# 2022_V2.net
KiCad netlist of a schematic drawn in Altium Designer
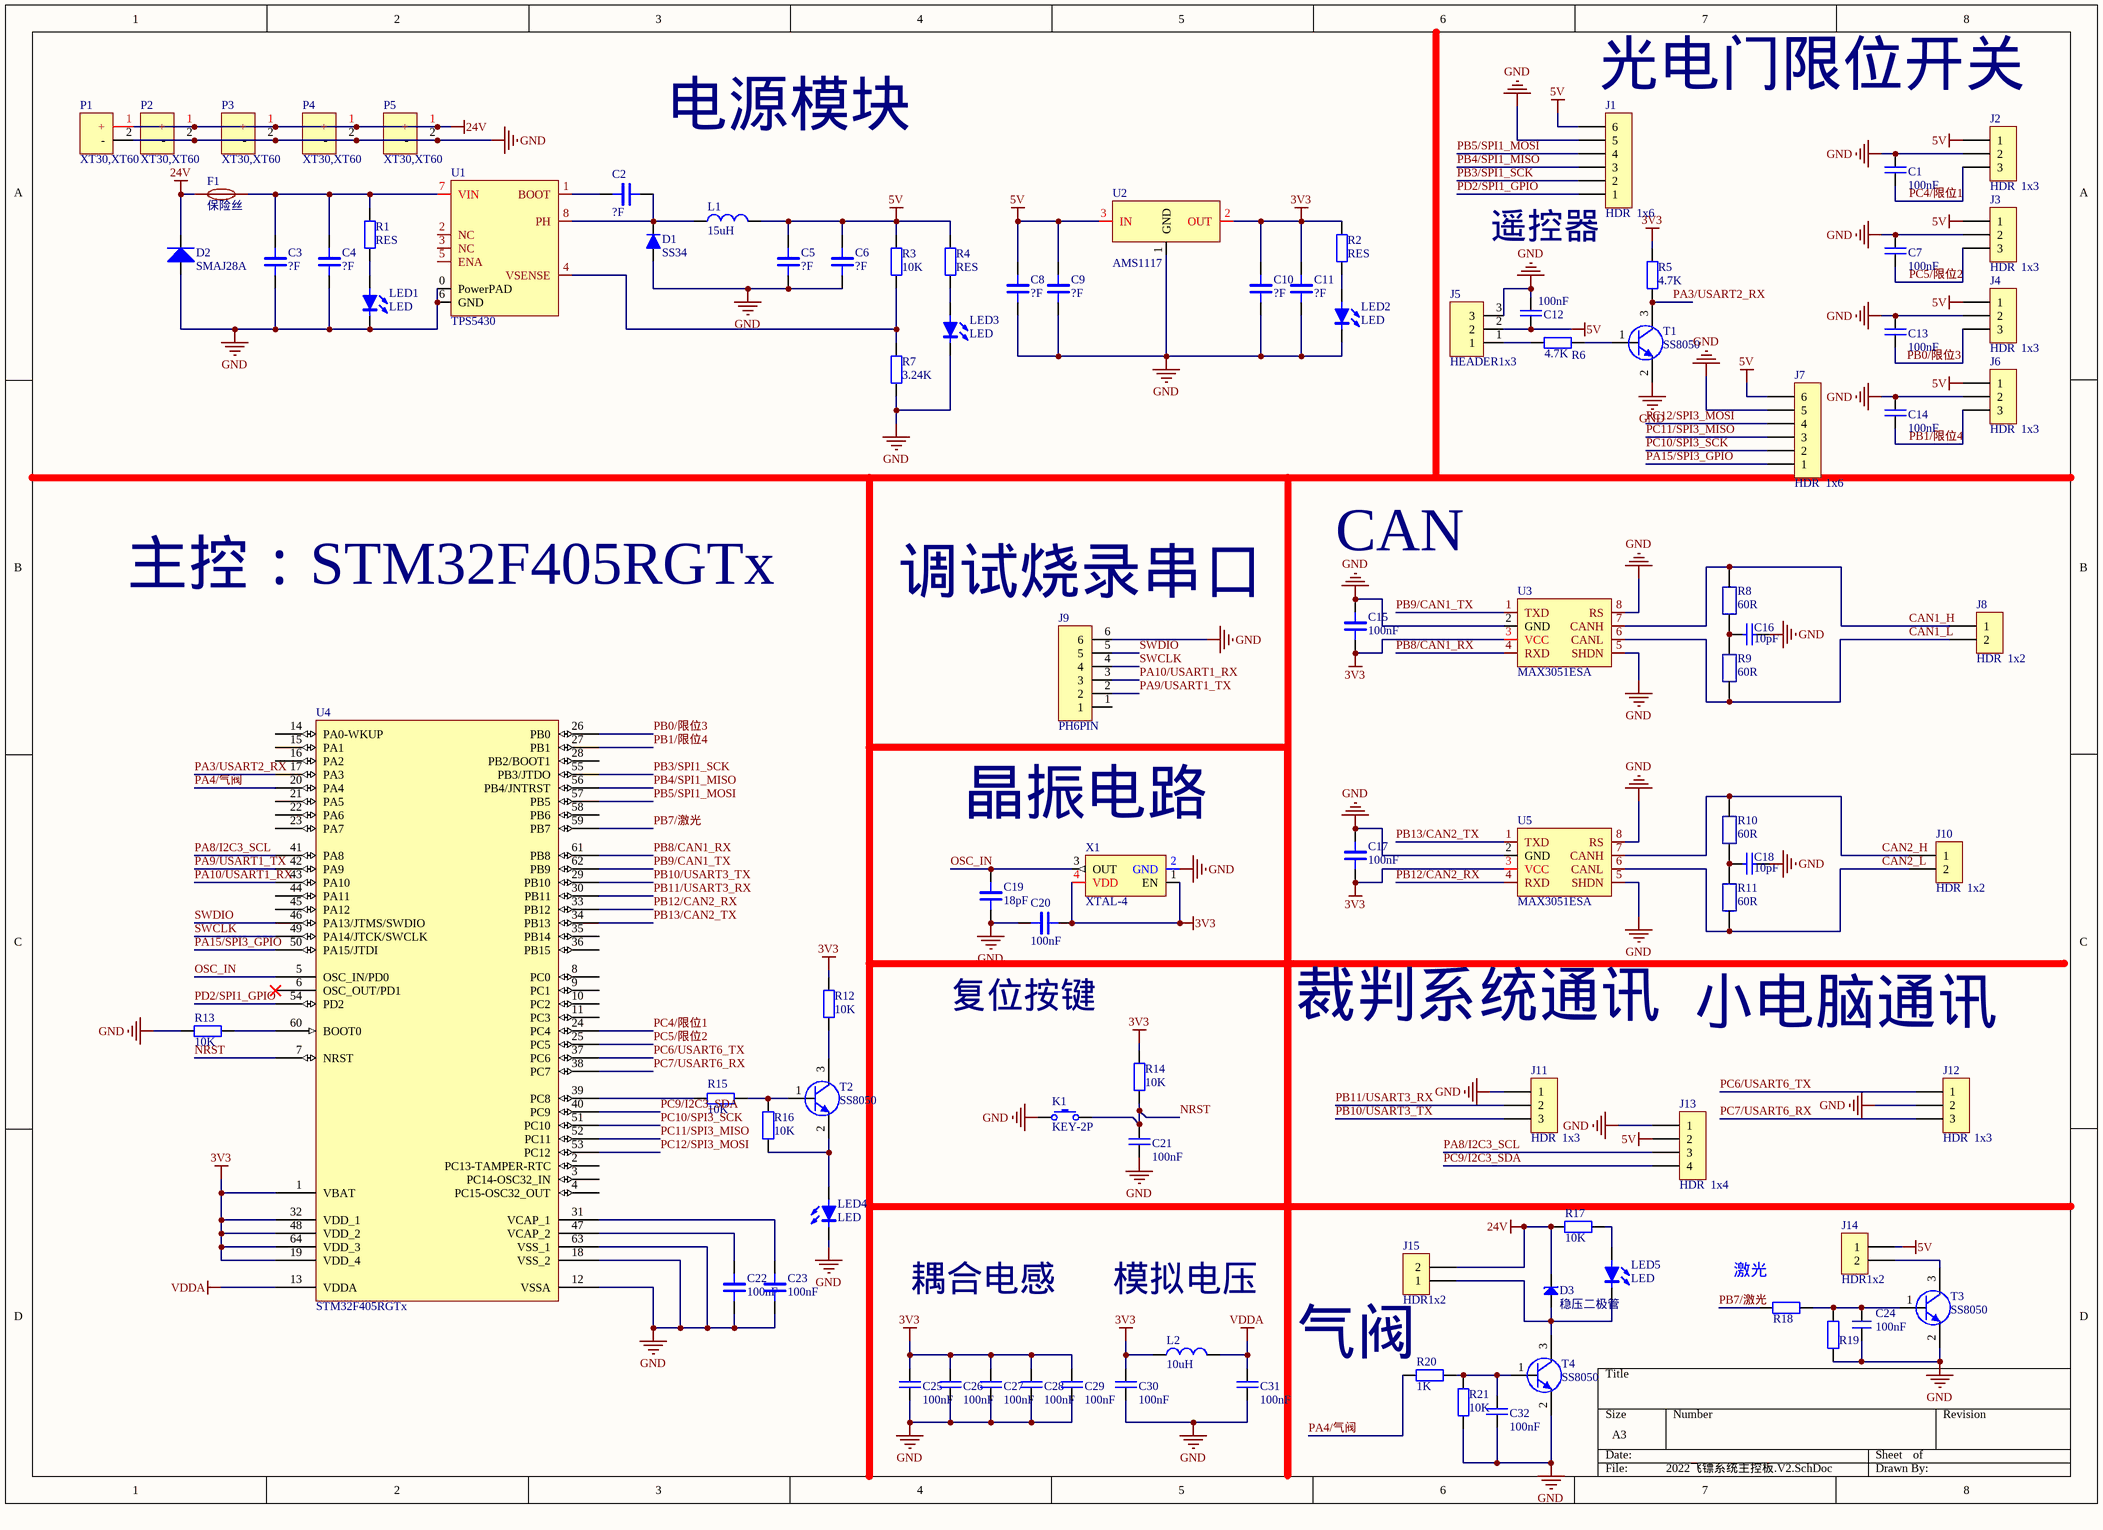
[diagram p0: 2022飞镖系统主控板.V2.SchDoc]

(export (version "E")
  (design (tool "Eeschema 10.0.6"))
  (components
    (comp (ref "C1")
      (value "100nF")
      (footprint "0603_C")
      (fields (field (name "PUBLISHER") "Altium Limited"))
      (libsource (lib "电容-电阻-电感") (part "Cap"))
    )
    (comp (ref "C2")
      (value "?F")
      (footprint "0603_C")
      (description "Capacitor")
      (libsource (lib "General（旧）") (part "CAP"))
    )
    (comp (ref "C3")
      (value "?F")
      (footprint "1206_C")
      (description "Capacitor")
      (libsource (lib "General（旧）") (part "CAP"))
    )
    (comp (ref "C4")
      (value "?F")
      (footprint "1206_C")
      (description "Capacitor")
      (libsource (lib "General（旧）") (part "CAP"))
    )
    (comp (ref "C5")
      (value "?F")
      (footprint "1206_C")
      (description "Capacitor")
      (libsource (lib "General（旧）") (part "CAP"))
    )
    (comp (ref "C6")
      (value "?F")
      (footprint "1206_C")
      (description "Capacitor")
      (libsource (lib "General（旧）") (part "CAP"))
    )
    (comp (ref "C7")
      (value "100nF")
      (footprint "0603_C")
      (fields (field (name "PUBLISHER") "Altium Limited"))
      (libsource (lib "电容-电阻-电感") (part "Cap"))
    )
    (comp (ref "C8")
      (value "?F")
      (footprint "1206_C")
      (description "Capacitor")
      (libsource (lib "General（旧）") (part "CAP"))
    )
    (comp (ref "C9")
      (value "?F")
      (footprint "1206_C")
      (description "Capacitor")
      (libsource (lib "General（旧）") (part "CAP"))
    )
    (comp (ref "C10")
      (value "?F")
      (footprint "1206_C")
      (description "Capacitor")
      (libsource (lib "General（旧）") (part "CAP"))
    )
    (comp (ref "C11")
      (value "?F")
      (footprint "1206_C")
      (description "Capacitor")
      (libsource (lib "General（旧）") (part "CAP"))
    )
    (comp (ref "C12")
      (value "100nF")
      (footprint "0603_C")
      (fields (field (name "PUBLISHER") "Altium Limited"))
      (libsource (lib "电容-电阻-电感") (part "Cap"))
    )
    (comp (ref "C13")
      (value "100nF")
      (footprint "0603_C")
      (fields (field (name "PUBLISHER") "Altium Limited"))
      (libsource (lib "电容-电阻-电感") (part "Cap"))
    )
    (comp (ref "C14")
      (value "100nF")
      (footprint "0603_C")
      (fields (field (name "PUBLISHER") "Altium Limited"))
      (libsource (lib "电容-电阻-电感") (part "Cap"))
    )
    (comp (ref "C15")
      (value "100nF")
      (footprint "0603_C")
      (description "Capacitor")
      (libsource (lib "General（旧）") (part "CAP"))
    )
    (comp (ref "C16") (value "10pF") (footprint "0603_C") (libsource (lib "原理图库") (part "C")))
    (comp (ref "C17")
      (value "100nF")
      (footprint "0603_C")
      (description "Capacitor")
      (libsource (lib "General（旧）") (part "CAP"))
    )
    (comp (ref "C18") (value "10pF") (footprint "0603_C") (libsource (lib "原理图库") (part "C")))
    (comp (ref "C19")
      (value "18pF")
      (footprint "0603_C")
      (description "Capacitor")
      (libsource (lib "General（旧）") (part "CAP"))
    )
    (comp (ref "C20")
      (value "100nF")
      (footprint "0603_C")
      (description "Capacitor")
      (libsource (lib "General（旧）") (part "CAP"))
    )
    (comp (ref "C21")
      (value "100nF")
      (footprint "0603_C")
      (fields (field (name "PUBLISHER") "Altium Limited"))
      (libsource (lib "电容-电阻-电感") (part "Cap"))
    )
    (comp (ref "C22")
      (value "100nF")
      (footprint "0603_C")
      (description "Capacitor")
      (libsource (lib "General（旧）") (part "CAP"))
    )
    (comp (ref "C23")
      (value "100nF")
      (footprint "0603_C")
      (description "Capacitor")
      (libsource (lib "General（旧）") (part "CAP"))
    )
    (comp (ref "C24")
      (value "100nF")
      (footprint "0603_C")
      (fields (field (name "PUBLISHER") "Altium Limited"))
      (libsource (lib "USUAUL") (part "Cap"))
    )
    (comp (ref "C25")
      (value "100nF")
      (footprint "0603_C")
      (fields (field (name "PUBLISHER") "Altium Limited"))
      (libsource (lib "电容-电阻-电感") (part "Cap"))
    )
    (comp (ref "C26")
      (value "100nF")
      (footprint "0603_C")
      (fields (field (name "PUBLISHER") "Altium Limited"))
      (libsource (lib "电容-电阻-电感") (part "Cap"))
    )
    (comp (ref "C27")
      (value "100nF")
      (footprint "0603_C")
      (fields (field (name "PUBLISHER") "Altium Limited"))
      (libsource (lib "电容-电阻-电感") (part "Cap"))
    )
    (comp (ref "C28")
      (value "100nF")
      (footprint "0603_C")
      (fields (field (name "PUBLISHER") "Altium Limited"))
      (libsource (lib "电容-电阻-电感") (part "Cap"))
    )
    (comp (ref "C29")
      (value "100nF")
      (footprint "0603_C")
      (fields (field (name "PUBLISHER") "Altium Limited"))
      (libsource (lib "电容-电阻-电感") (part "Cap"))
    )
    (comp (ref "C30")
      (value "100nF")
      (footprint "0603_C")
      (fields (field (name "PUBLISHER") "Altium Limited"))
      (libsource (lib "电容-电阻-电感") (part "Cap"))
    )
    (comp (ref "C31")
      (value "100nF")
      (footprint "0603_C")
      (fields (field (name "PUBLISHER") "Altium Limited"))
      (libsource (lib "电容-电阻-电感") (part "Cap"))
    )
    (comp (ref "C32")
      (value "100nF")
      (footprint "0603_C")
      (fields (field (name "PUBLISHER") "Altium Limited"))
      (libsource (lib "电容-电阻-电感") (part "Cap"))
    )
    (comp (ref "D1")
      (value "SS34")
      (footprint "SMA(DO-214AC)")
      (description "肖特基二极管")
      (fields
        (field (name "BOM_SUPPLIER PART") "C431540")
        (field (name "BOM_MANUFACTURER PART") "MSK12C02")
        (field (name "CONTRIBUTOR") "LCSC")
      )
      (libsource (lib "General（旧）") (part "SS34"))
    )
    (comp (ref "D2")
      (value "SMAJ28A")
      (footprint "SMA(DO-214AC)")
      (description "TVS")
      (libsource (lib "General（旧）") (part "SMAJ28A"))
    )
    (comp (ref "D3") (value "稳压二极管") (footprint "SOD-323") (libsource (lib "General（旧）") (part "稳压二极管")))
    (comp (ref "F1") (value "保险丝") (footprint "1812_F") (libsource (lib "General（旧）") (part "保险丝")))
    (comp (ref "J1")
      (value "HDR  1x6")
      (footprint "GH 6P 1.25mm 卧 贴")
      (description "Connector")
      (libsource (lib "General（旧）") (part "HDR  1x6"))
    )
    (comp (ref "J2")
      (value "HDR  1x3")
      (footprint "PH 3P 2mm 立 插")
      (description "Connector")
      (libsource (lib "General（旧）") (part "HDR  1x3"))
    )
    (comp (ref "J3")
      (value "HDR  1x3")
      (footprint "PH 3P 2mm 立 插")
      (description "Connector")
      (libsource (lib "General（旧）") (part "HDR  1x3"))
    )
    (comp (ref "J4")
      (value "HDR  1x3")
      (footprint "PH 3P 2mm 立 插")
      (description "Connector")
      (libsource (lib "General（旧）") (part "HDR  1x3"))
    )
    (comp (ref "J5")
      (value "HEADER1x3")
      (footprint "GH 3P 1.25mm 卧 贴")
      (libsource (lib "连接器") (part "HEADER1x3"))
    )
    (comp (ref "J6")
      (value "HDR  1x3")
      (footprint "PH 3P 2mm 立 插")
      (description "Connector")
      (libsource (lib "General（旧）") (part "HDR  1x3"))
    )
    (comp (ref "J7")
      (value "HDR  1x6")
      (footprint "GH 6P 1.25mm 卧 贴")
      (description "Connector")
      (libsource (lib "General（旧）") (part "HDR  1x6"))
    )
    (comp (ref "J8")
      (value "HDR  1x2")
      (footprint "GH 2P 1.25mm 卧 贴")
      (description "Connector")
      (libsource (lib "General（旧）") (part "HDR  1x2"))
    )
    (comp (ref "J9") (value "PH6PIN") (footprint "PH 6P 2mm 立 插") (libsource (lib "连接器") (part "PH 6P")))
    (comp (ref "J10")
      (value "HDR  1x2")
      (footprint "GH 2P 1.25mm 卧 贴")
      (description "Connector")
      (libsource (lib "General（旧）") (part "HDR  1x2"))
    )
    (comp (ref "J11")
      (value "HDR  1x3")
      (footprint "GH 3P 1.25mm 卧 贴")
      (description "Connector")
      (libsource (lib "General（旧）") (part "HDR  1x3"))
    )
    (comp (ref "J12")
      (value "HDR  1x3")
      (footprint "GH 3P 1.25mm 卧 贴")
      (description "Connector")
      (libsource (lib "General（旧）") (part "HDR  1x3"))
    )
    (comp (ref "J13")
      (value "HDR  1x4")
      (footprint "排针排母 4P 2.54mm")
      (description "Connector")
      (libsource (lib "General（旧）") (part "HDR  1x4"))
    )
    (comp (ref "J14")
      (value "HDR1x2")
      (footprint "FPC-SMD_2P-P2.00_DEALON_PH-2PWB")
      (description "Connector")
      (libsource (lib "General") (part "HDR1x2"))
    )
    (comp (ref "J15")
      (value "HDR1x2")
      (footprint "FPC-SMD_2P-P2.00_DEALON_PH-2PWB")
      (description "Connector")
      (libsource (lib "") (part "HDR1x2_1"))
    )
    (comp (ref "K1")
      (value "KEY-2P")
      (footprint "SW-按键")
      (description "Key")
      (libsource (lib "General") (part "KEY-2P"))
    )
    (comp (ref "L1")
      (value "15uH")
      (footprint "SMD_7.3*6.6*3MM_0630")
      (description "Inductor")
      (fields (field (name "PUBLISHER") "Altium Limited"))
      (libsource (lib "General（旧）") (part "Inductor"))
    )
    (comp (ref "L2")
      (value "10uH")
      (footprint "0603_L")
      (description "Inductor")
      (fields (field (name "PUBLISHER") "Altium Limited"))
      (libsource (lib "General（旧）") (part "Inductor"))
    )
    (comp (ref "LED1") (value "LED") (footprint "LED_0603") (libsource (lib "General（旧）") (part "LED")))
    (comp (ref "LED2") (value "LED") (footprint "LED_0603") (libsource (lib "General（旧）") (part "LED")))
    (comp (ref "LED3") (value "LED") (footprint "LED_0603") (libsource (lib "General（旧）") (part "LED")))
    (comp (ref "LED4") (value "LED") (footprint "LED_0603") (libsource (lib "General（旧）") (part "LED")))
    (comp (ref "LED5") (value "LED") (footprint "LED_0603") (libsource (lib "General（旧）") (part "LED")))
    (comp (ref "P1")
      (value "XT30,XT60")
      (footprint "XT30PW-F")
      (description "电源接口")
      (libsource (lib "General（旧）") (part "XT"))
    )
    (comp (ref "P2")
      (value "XT30,XT60")
      (footprint "XT30PW-F")
      (description "电源接口")
      (libsource (lib "General（旧）") (part "XT"))
    )
    (comp (ref "P3")
      (value "XT30,XT60")
      (footprint "XT30PW-F")
      (description "电源接口")
      (libsource (lib "General（旧）") (part "XT"))
    )
    (comp (ref "P4")
      (value "XT30,XT60")
      (footprint "XT30PW-F")
      (description "电源接口")
      (libsource (lib "General（旧）") (part "XT"))
    )
    (comp (ref "P5")
      (value "XT30,XT60")
      (footprint "XT30PW-F")
      (description "电源接口")
      (libsource (lib "General（旧）") (part "XT"))
    )
    (comp (ref "R1")
      (value "RES")
      (footprint "0603_R")
      (description "Resistor")
      (libsource (lib "") (part "RES_1"))
    )
    (comp (ref "R2")
      (value "RES")
      (footprint "0603_R")
      (description "Resistor")
      (libsource (lib "") (part "RES_1"))
    )
    (comp (ref "R3")
      (value "10K")
      (footprint "0603_R")
      (description "Resistor")
      (libsource (lib "") (part "RES_1"))
    )
    (comp (ref "R4")
      (value "RES")
      (footprint "0603_R")
      (description "Resistor")
      (libsource (lib "") (part "RES_1"))
    )
    (comp (ref "R5")
      (value "4.7K")
      (footprint "0603_R")
      (fields (field (name "PUBLISHER") "Altium Limited"))
      (libsource (lib "") (part "Res_1"))
    )
    (comp (ref "R6")
      (value "4.7K")
      (footprint "0603_R")
      (fields (field (name "PUBLISHER") "Altium Limited"))
      (libsource (lib "") (part "Res_2"))
    )
    (comp (ref "R7")
      (value "3.24K")
      (footprint "0603_R")
      (description "Resistor")
      (libsource (lib "") (part "RES_1"))
    )
    (comp (ref "R8") (value "60R") (footprint "0603_R") (libsource (lib "原理图库") (part "R")))
    (comp (ref "R9") (value "60R") (footprint "0603_R") (libsource (lib "原理图库") (part "R")))
    (comp (ref "R10") (value "60R") (footprint "0603_R") (libsource (lib "原理图库") (part "R")))
    (comp (ref "R11") (value "60R") (footprint "0603_R") (libsource (lib "原理图库") (part "R")))
    (comp (ref "R12")
      (value "10K")
      (footprint "0603_R")
      (description "Resistor")
      (libsource (lib "") (part "RES_3"))
    )
    (comp (ref "R13")
      (value "10K")
      (footprint "0603_R")
      (description "Resistor")
      (libsource (lib "General（旧）") (part "RES"))
    )
    (comp (ref "R14")
      (value "10K")
      (footprint "0603_R")
      (fields (field (name "PUBLISHER") "Altium Limited"))
      (libsource (lib "") (part "Res_1"))
    )
    (comp (ref "R15")
      (value "10K")
      (footprint "0603_R")
      (description "Resistor")
      (libsource (lib "") (part "RES_2"))
    )
    (comp (ref "R16")
      (value "10K")
      (footprint "0603_R")
      (description "Resistor")
      (libsource (lib "General（旧）") (part "RES"))
    )
    (comp (ref "R17")
      (value "10K")
      (footprint "0603_R")
      (fields (field (name "PUBLISHER") "Altium Limited"))
      (libsource (lib "电容-电阻-电感") (part "Res"))
    )
    (comp (ref "R18")
      (value "Res")
      (footprint "0603_R")
      (fields (field (name "PUBLISHER") "Altium Limited"))
      (libsource (lib "电容-电阻-电感") (part "Res"))
    )
    (comp (ref "R19")
      (value "Res")
      (footprint "0603_R")
      (fields (field (name "PUBLISHER") "Altium Limited"))
      (libsource (lib "") (part "Res_1"))
    )
    (comp (ref "R20")
      (value "1K")
      (footprint "0603_R")
      (fields (field (name "PUBLISHER") "Altium Limited"))
      (libsource (lib "电容-电阻-电感") (part "Res"))
    )
    (comp (ref "R21")
      (value "10K")
      (footprint "0603_R")
      (fields (field (name "PUBLISHER") "Altium Limited"))
      (libsource (lib "") (part "Res_1"))
    )
    (comp (ref "T1")
      (value "SS8050")
      (footprint "SOT-23")
      (description "NPN")
      (fields (field (name "PUBLISHER") "Altium Limited"))
      (libsource (lib "二极管-晶体管") (part "SS8050"))
    )
    (comp (ref "T2")
      (value "SS8050")
      (footprint "SOT-23")
      (description "NPN")
      (fields (field (name "PUBLISHER") "Altium Limited"))
      (libsource (lib "二极管-晶体管") (part "SS8050"))
    )
    (comp (ref "T3")
      (value "SS8050")
      (footprint "SOT-23")
      (description "NPN")
      (fields (field (name "PUBLISHER") "Altium Limited"))
      (libsource (lib "二极管-晶体管") (part "SS8050"))
    )
    (comp (ref "T4")
      (value "SS8050")
      (footprint "SOT-23")
      (description "NPN")
      (fields (field (name "PUBLISHER") "Altium Limited"))
      (libsource (lib "二极管-晶体管") (part "SS8050"))
    )
    (comp (ref "U1")
      (value "TPS5430")
      (footprint "SOP8-EP")
      (description "DC-DC 降压芯片")
      (libsource (lib "General（旧）") (part "TPS5430"))
    )
    (comp (ref "U2")
      (value "AMS1117")
      (footprint "SOT-223")
      (description "LDO")
      (libsource (lib "General（旧）") (part "AMS1117"))
    )
    (comp (ref "U3")
      (value "MAX3051ESA")
      (footprint "SOP8")
      (description "CAN芯片")
      (libsource (lib "General（旧）") (part "MAX3051ESA"))
    )
    (comp (ref "U4")
      (value "STM32F405RGTx")
      (footprint "LQFP-64_10x10x05P")
      (description "STM32单片机")
      (libsource (lib "General（旧）") (part "STM32F405RGTx"))
    )
    (comp (ref "U5")
      (value "MAX3051ESA")
      (footprint "SOP8")
      (description "CAN芯片")
      (libsource (lib "General（旧）") (part "MAX3051ESA"))
    )
    (comp (ref "X1")
      (value "XTAL-4")
      (footprint "OSC-SMD_4P")
      (description "Oscillator")
      (libsource (lib "General（旧）") (part "XTAL-4"))
    )
  )
  (nets
    (net (code "1") (name "/CAN1_H") (class "Default")
      (node (ref "J8") (pin "1") (pinfunction "1_1") (pintype "passive"))
      (node (ref "R8") (pin "2") (pinfunction "2_2") (pintype "passive"))
      (node (ref "U3") (pin "7") (pinfunction "CANH_7") (pintype "passive"))
    )
    (net (code "2") (name "/CAN1_L") (class "Default")
      (node (ref "J8") (pin "2") (pinfunction "2_2") (pintype "passive"))
      (node (ref "R9") (pin "2") (pinfunction "2_2") (pintype "passive"))
      (node (ref "U3") (pin "6") (pinfunction "CANL_6") (pintype "passive"))
    )
    (net (code "3") (name "/CAN2_H") (class "Default")
      (node (ref "J10") (pin "1") (pinfunction "1_1") (pintype "passive"))
      (node (ref "R10") (pin "2") (pinfunction "2_2") (pintype "passive"))
      (node (ref "U5") (pin "7") (pinfunction "CANH_7") (pintype "passive"))
    )
    (net (code "4") (name "/CAN2_L") (class "Default")
      (node (ref "J10") (pin "2") (pinfunction "2_2") (pintype "passive"))
      (node (ref "R11") (pin "2") (pinfunction "2_2") (pintype "passive"))
      (node (ref "U5") (pin "6") (pinfunction "CANL_6") (pintype "passive"))
    )
    (net (code "5") (name "/NRST") (class "Default")
      (node (ref "C21") (pin "1") (pinfunction "1_1") (pintype "passive"))
      (node (ref "K1") (pin "2") (pinfunction "2_2") (pintype "passive"))
      (node (ref "R14") (pin "1") (pinfunction "1_1") (pintype "passive"))
      (node (ref "U4") (pin "7") (pinfunction "NRST_7") (pintype "bidirectional"))
    )
    (net (code "6") (name "/OSC_IN") (class "Default")
      (node (ref "C19") (pin "2") (pinfunction "2_2") (pintype "passive"))
      (node (ref "U4") (pin "5") (pinfunction "OSC_IN/PD0_5") (pintype "passive"))
      (node (ref "X1") (pin "3") (pinfunction "OUT_3") (pintype "output"))
    )
    (net (code "7") (name "/PA3{slash}USART2_RX") (class "Default")
      (node (ref "R5") (pin "1") (pinfunction "1_1") (pintype "passive"))
      (node (ref "T1") (pin "3") (pinfunction "C_3") (pintype "passive"))
      (node (ref "U4") (pin "17") (pinfunction "PA3_17") (pintype "bidirectional"))
    )
    (net (code "8") (name "/PA4{slash}气阀") (class "Default")
      (node (ref "R20") (pin "1") (pinfunction "1_1") (pintype "passive"))
      (node (ref "U4") (pin "20") (pinfunction "PA4_20") (pintype "bidirectional"))
    )
    (net (code "9") (name "/PA8{slash}I2C3_SCL") (class "Default")
      (node (ref "J13") (pin "3") (pinfunction "3_3") (pintype "passive"))
      (node (ref "U4") (pin "41") (pinfunction "PA8_41") (pintype "bidirectional"))
    )
    (net (code "10") (name "/PA9{slash}USART1_TX") (class "Default")
      (node (ref "J9") (pin "2") (pinfunction "2_2") (pintype "passive"))
      (node (ref "U4") (pin "42") (pinfunction "PA9_42") (pintype "bidirectional"))
    )
    (net (code "11") (name "/PA10{slash}USART1_RX") (class "Default")
      (node (ref "J9") (pin "3") (pinfunction "3_3") (pintype "passive"))
      (node (ref "U4") (pin "43") (pinfunction "PA10_43") (pintype "bidirectional"))
    )
    (net (code "12") (name "/PA15{slash}SPI3_GPIO") (class "Default")
      (node (ref "J7") (pin "1") (pinfunction "1_1") (pintype "passive"))
      (node (ref "U4") (pin "50") (pinfunction "PA15/JTDI_50") (pintype "bidirectional"))
    )
    (net (code "13") (name "/PB0{slash}限位3") (class "Default")
      (node (ref "C13") (pin "2") (pinfunction "2_2") (pintype "passive"))
      (node (ref "J4") (pin "3") (pinfunction "3_3") (pintype "passive"))
      (node (ref "U4") (pin "26") (pinfunction "PB0_26") (pintype "bidirectional"))
    )
    (net (code "14") (name "/PB1{slash}限位4") (class "Default")
      (node (ref "C14") (pin "2") (pinfunction "2_2") (pintype "passive"))
      (node (ref "J6") (pin "3") (pinfunction "3_3") (pintype "passive"))
      (node (ref "U4") (pin "27") (pinfunction "PB1_27") (pintype "bidirectional"))
    )
    (net (code "15") (name "/PB3{slash}SPI1_SCK") (class "Default")
      (node (ref "J1") (pin "2") (pinfunction "2_2") (pintype "passive"))
      (node (ref "U4") (pin "55") (pinfunction "PB3/JTDO_55") (pintype "bidirectional"))
    )
    (net (code "16") (name "/PB4{slash}SPI1_MISO") (class "Default")
      (node (ref "J1") (pin "3") (pinfunction "3_3") (pintype "passive"))
      (node (ref "U4") (pin "56") (pinfunction "PB4/JNTRST_56") (pintype "bidirectional"))
    )
    (net (code "17") (name "/PB5{slash}SPI1_MOSI") (class "Default")
      (node (ref "J1") (pin "4") (pinfunction "4_4") (pintype "passive"))
      (node (ref "U4") (pin "57") (pinfunction "PB5_57") (pintype "bidirectional"))
    )
    (net (code "18") (name "/PB7{slash}激光") (class "Default")
      (node (ref "R18") (pin "1") (pinfunction "1_1") (pintype "passive"))
      (node (ref "U4") (pin "59") (pinfunction "PB7_59") (pintype "bidirectional"))
    )
    (net (code "19") (name "/PB8{slash}CAN1_RX") (class "Default")
      (node (ref "U3") (pin "4") (pinfunction "RXD_4") (pintype "passive"))
      (node (ref "U4") (pin "61") (pinfunction "PB8_61") (pintype "bidirectional"))
    )
    (net (code "20") (name "/PB9{slash}CAN1_TX") (class "Default")
      (node (ref "U3") (pin "1") (pinfunction "TXD_1") (pintype "passive"))
      (node (ref "U4") (pin "62") (pinfunction "PB9_62") (pintype "bidirectional"))
    )
    (net (code "21") (name "/PB10{slash}USART3_TX") (class "Default")
      (node (ref "J11") (pin "3") (pinfunction "3_3") (pintype "passive"))
      (node (ref "U4") (pin "29") (pinfunction "PB10_29") (pintype "bidirectional"))
    )
    (net (code "22") (name "/PB11{slash}USART3_RX") (class "Default")
      (node (ref "J11") (pin "2") (pinfunction "2_2") (pintype "passive"))
      (node (ref "U4") (pin "30") (pinfunction "PB11_30") (pintype "bidirectional"))
    )
    (net (code "23") (name "/PB12{slash}CAN2_RX") (class "Default")
      (node (ref "U4") (pin "33") (pinfunction "PB12_33") (pintype "bidirectional"))
      (node (ref "U5") (pin "4") (pinfunction "RXD_4") (pintype "passive"))
    )
    (net (code "24") (name "/PB13{slash}CAN2_TX") (class "Default")
      (node (ref "U4") (pin "34") (pinfunction "PB13_34") (pintype "bidirectional"))
      (node (ref "U5") (pin "1") (pinfunction "TXD_1") (pintype "passive"))
    )
    (net (code "25") (name "/PC4{slash}限位1") (class "Default")
      (node (ref "C1") (pin "2") (pinfunction "2_2") (pintype "passive"))
      (node (ref "J2") (pin "3") (pinfunction "3_3") (pintype "passive"))
      (node (ref "U4") (pin "24") (pinfunction "PC4_24") (pintype "bidirectional"))
    )
    (net (code "26") (name "/PC5{slash}限位2") (class "Default")
      (node (ref "C7") (pin "2") (pinfunction "2_2") (pintype "passive"))
      (node (ref "J3") (pin "3") (pinfunction "3_3") (pintype "passive"))
      (node (ref "U4") (pin "25") (pinfunction "PC5_25") (pintype "bidirectional"))
    )
    (net (code "27") (name "/PC6{slash}USART6_TX") (class "Default")
      (node (ref "J12") (pin "1") (pinfunction "1_1") (pintype "passive"))
      (node (ref "U4") (pin "37") (pinfunction "PC6_37") (pintype "bidirectional"))
    )
    (net (code "28") (name "/PC7{slash}USART6_RX") (class "Default")
      (node (ref "J12") (pin "3") (pinfunction "3_3") (pintype "passive"))
      (node (ref "U4") (pin "38") (pinfunction "PC7_38") (pintype "bidirectional"))
    )
    (net (code "29") (name "/PC9{slash}I2C3_SDA") (class "Default")
      (node (ref "J13") (pin "4") (pinfunction "4_4") (pintype "passive"))
      (node (ref "U4") (pin "40") (pinfunction "PC9_40") (pintype "bidirectional"))
    )
    (net (code "30") (name "/PC10{slash}SPI3_SCK") (class "Default")
      (node (ref "J7") (pin "2") (pinfunction "2_2") (pintype "passive"))
      (node (ref "U4") (pin "51") (pinfunction "PC10_51") (pintype "bidirectional"))
    )
    (net (code "31") (name "/PC11{slash}SPI3_MISO") (class "Default")
      (node (ref "J7") (pin "3") (pinfunction "3_3") (pintype "passive"))
      (node (ref "U4") (pin "52") (pinfunction "PC11_52") (pintype "bidirectional"))
    )
    (net (code "32") (name "/PC12{slash}SPI3_MOSI") (class "Default")
      (node (ref "J7") (pin "4") (pinfunction "4_4") (pintype "passive"))
      (node (ref "U4") (pin "53") (pinfunction "PC12_53") (pintype "bidirectional"))
    )
    (net (code "33") (name "/PD2{slash}SPI1_GPIO") (class "Default")
      (node (ref "J1") (pin "1") (pinfunction "1_1") (pintype "passive"))
      (node (ref "U4") (pin "54") (pinfunction "PD2_54") (pintype "bidirectional"))
    )
    (net (code "34") (name "/SWCLK") (class "Default")
      (node (ref "J9") (pin "4") (pinfunction "4_4") (pintype "passive"))
      (node (ref "U4") (pin "49") (pinfunction "PA14/JTCK/SWCLK_49") (pintype "bidirectional"))
    )
    (net (code "35") (name "/SWDIO") (class "Default")
      (node (ref "J9") (pin "5") (pinfunction "5_5") (pintype "passive"))
      (node (ref "U4") (pin "46") (pinfunction "PA13/JTMS/SWDIO_46") (pintype "bidirectional"))
    )
    (net (code "36") (name "3V3") (class "Default")
      (node (ref "C10") (pin "2") (pinfunction "2_2") (pintype "passive"))
      (node (ref "C11") (pin "2") (pinfunction "2_2") (pintype "passive"))
      (node (ref "C15") (pin "2") (pinfunction "2_2") (pintype "passive"))
      (node (ref "C17") (pin "2") (pinfunction "2_2") (pintype "passive"))
      (node (ref "C20") (pin "2") (pinfunction "2_2") (pintype "passive"))
      (node (ref "C25") (pin "1") (pinfunction "1_1") (pintype "passive"))
      (node (ref "C26") (pin "1") (pinfunction "1_1") (pintype "passive"))
      (node (ref "C27") (pin "1") (pinfunction "1_1") (pintype "passive"))
      (node (ref "C28") (pin "1") (pinfunction "1_1") (pintype "passive"))
      (node (ref "C29") (pin "1") (pinfunction "1_1") (pintype "passive"))
      (node (ref "C30") (pin "1") (pinfunction "1_1") (pintype "passive"))
      (node (ref "L2") (pin "1") (pinfunction "1_1") (pintype "passive"))
      (node (ref "R12") (pin "1") (pinfunction "1_1") (pintype "passive"))
      (node (ref "R14") (pin "2") (pinfunction "2_2") (pintype "passive"))
      (node (ref "R2") (pin "2") (pinfunction "2_2") (pintype "passive"))
      (node (ref "R5") (pin "2") (pinfunction "2_2") (pintype "passive"))
      (node (ref "U2") (pin "2") (pinfunction "OUT_2") (pintype "passive"))
      (node (ref "U3") (pin "3") (pinfunction "VCC_3") (pintype "passive"))
      (node (ref "U4") (pin "1") (pinfunction "VBAT_1") (pintype "power_in"))
      (node (ref "U4") (pin "19") (pinfunction "VDD_4_19") (pintype "power_in"))
      (node (ref "U4") (pin "32") (pinfunction "VDD_1_32") (pintype "power_in"))
      (node (ref "U4") (pin "48") (pinfunction "VDD_2_48") (pintype "power_in"))
      (node (ref "U4") (pin "64") (pinfunction "VDD_3_64") (pintype "power_in"))
      (node (ref "U5") (pin "3") (pinfunction "VCC_3") (pintype "passive"))
      (node (ref "X1") (pin "1") (pinfunction "EN_1") (pintype "passive"))
      (node (ref "X1") (pin "4") (pinfunction "VDD_4") (pintype "power_in"))
    )
    (net (code "37") (name "5V") (class "Default")
      (node (ref "C12") (pin "1") (pinfunction "1_1") (pintype "passive"))
      (node (ref "C5") (pin "2") (pinfunction "2_2") (pintype "passive"))
      (node (ref "C6") (pin "2") (pinfunction "2_2") (pintype "passive"))
      (node (ref "C8") (pin "2") (pinfunction "2_2") (pintype "passive"))
      (node (ref "C9") (pin "2") (pinfunction "2_2") (pintype "passive"))
      (node (ref "J1") (pin "6") (pinfunction "6_6") (pintype "passive"))
      (node (ref "J13") (pin "2") (pinfunction "2_2") (pintype "passive"))
      (node (ref "J14") (pin "1") (pinfunction "1_1") (pintype "passive"))
      (node (ref "J2") (pin "1") (pinfunction "1_1") (pintype "passive"))
      (node (ref "J3") (pin "1") (pinfunction "1_1") (pintype "passive"))
      (node (ref "J4") (pin "1") (pinfunction "1_1") (pintype "passive"))
      (node (ref "J5") (pin "2") (pinfunction "2_2") (pintype "passive"))
      (node (ref "J6") (pin "1") (pinfunction "1_1") (pintype "passive"))
      (node (ref "J7") (pin "6") (pinfunction "6_6") (pintype "passive"))
      (node (ref "L1") (pin "2") (pinfunction "2_2") (pintype "passive"))
      (node (ref "R3") (pin "2") (pinfunction "2_2") (pintype "passive"))
      (node (ref "R4") (pin "2") (pinfunction "2_2") (pintype "passive"))
      (node (ref "U2") (pin "3") (pinfunction "IN_3") (pintype "passive"))
    )
    (net (code "38") (name "24V") (class "Default")
      (node (ref "D2") (pin "2") (pinfunction "K_2") (pintype "passive"))
      (node (ref "D3") (pin "2") (pinfunction "K_2") (pintype "passive"))
      (node (ref "F1") (pin "1") (pinfunction "1_1") (pintype "passive"))
      (node (ref "J15") (pin "2") (pinfunction "2_2") (pintype "passive"))
      (node (ref "P1") (pin "1") (pinfunction "+_1") (pintype "passive"))
      (node (ref "P2") (pin "1") (pinfunction "+_1") (pintype "passive"))
      (node (ref "P3") (pin "1") (pinfunction "+_1") (pintype "passive"))
      (node (ref "P4") (pin "1") (pinfunction "+_1") (pintype "passive"))
      (node (ref "P5") (pin "1") (pinfunction "+_1") (pintype "passive"))
      (node (ref "R17") (pin "1") (pinfunction "1_1") (pintype "passive"))
    )
    (net (code "39") (name "GND") (class "Default")
      (node (ref "C1") (pin "1") (pinfunction "1_1") (pintype "passive"))
      (node (ref "C10") (pin "1") (pinfunction "1_1") (pintype "passive"))
      (node (ref "C11") (pin "1") (pinfunction "1_1") (pintype "passive"))
      (node (ref "C12") (pin "2") (pinfunction "2_2") (pintype "passive"))
      (node (ref "C13") (pin "1") (pinfunction "1_1") (pintype "passive"))
      (node (ref "C14") (pin "1") (pinfunction "1_1") (pintype "passive"))
      (node (ref "C15") (pin "1") (pinfunction "1_1") (pintype "passive"))
      (node (ref "C16") (pin "2") (pinfunction "2_2") (pintype "passive"))
      (node (ref "C17") (pin "1") (pinfunction "1_1") (pintype "passive"))
      (node (ref "C18") (pin "2") (pinfunction "2_2") (pintype "passive"))
      (node (ref "C19") (pin "1") (pinfunction "1_1") (pintype "passive"))
      (node (ref "C20") (pin "1") (pinfunction "1_1") (pintype "passive"))
      (node (ref "C21") (pin "2") (pinfunction "2_2") (pintype "passive"))
      (node (ref "C22") (pin "1") (pinfunction "1_1") (pintype "passive"))
      (node (ref "C23") (pin "1") (pinfunction "1_1") (pintype "passive"))
      (node (ref "C24") (pin "1") (pinfunction "1_1") (pintype "passive"))
      (node (ref "C25") (pin "2") (pinfunction "2_2") (pintype "passive"))
      (node (ref "C26") (pin "2") (pinfunction "2_2") (pintype "passive"))
      (node (ref "C27") (pin "2") (pinfunction "2_2") (pintype "passive"))
      (node (ref "C28") (pin "2") (pinfunction "2_2") (pintype "passive"))
      (node (ref "C29") (pin "2") (pinfunction "2_2") (pintype "passive"))
      (node (ref "C3") (pin "1") (pinfunction "1_1") (pintype "passive"))
      (node (ref "C30") (pin "2") (pinfunction "2_2") (pintype "passive"))
      (node (ref "C31") (pin "2") (pinfunction "2_2") (pintype "passive"))
      (node (ref "C32") (pin "2") (pinfunction "2_2") (pintype "passive"))
      (node (ref "C4") (pin "1") (pinfunction "1_1") (pintype "passive"))
      (node (ref "C5") (pin "1") (pinfunction "1_1") (pintype "passive"))
      (node (ref "C6") (pin "1") (pinfunction "1_1") (pintype "passive"))
      (node (ref "C7") (pin "1") (pinfunction "1_1") (pintype "passive"))
      (node (ref "C8") (pin "1") (pinfunction "1_1") (pintype "passive"))
      (node (ref "C9") (pin "1") (pinfunction "1_1") (pintype "passive"))
      (node (ref "D1") (pin "1") (pinfunction "1_1") (pintype "passive"))
      (node (ref "D2") (pin "1") (pinfunction "A_1") (pintype "passive"))
      (node (ref "J1") (pin "5") (pinfunction "5_5") (pintype "passive"))
      (node (ref "J11") (pin "1") (pinfunction "1_1") (pintype "passive"))
      (node (ref "J12") (pin "2") (pinfunction "2_2") (pintype "passive"))
      (node (ref "J13") (pin "1") (pinfunction "1_1") (pintype "passive"))
      (node (ref "J2") (pin "2") (pinfunction "2_2") (pintype "passive"))
      (node (ref "J3") (pin "2") (pinfunction "2_2") (pintype "passive"))
      (node (ref "J4") (pin "2") (pinfunction "2_2") (pintype "passive"))
      (node (ref "J5") (pin "3") (pinfunction "3_3") (pintype "passive"))
      (node (ref "J6") (pin "2") (pinfunction "2_2") (pintype "passive"))
      (node (ref "J7") (pin "5") (pinfunction "5_5") (pintype "passive"))
      (node (ref "J9") (pin "6") (pinfunction "6_6") (pintype "passive"))
      (node (ref "K1") (pin "1") (pinfunction "1_1") (pintype "passive"))
      (node (ref "LED1") (pin "2") (pinfunction "C_2") (pintype "passive"))
      (node (ref "LED2") (pin "2") (pinfunction "C_2") (pintype "passive"))
      (node (ref "LED3") (pin "2") (pinfunction "C_2") (pintype "passive"))
      (node (ref "LED4") (pin "2") (pinfunction "C_2") (pintype "passive"))
      (node (ref "P1") (pin "2") (pinfunction "-_2") (pintype "passive"))
      (node (ref "P2") (pin "2") (pinfunction "-_2") (pintype "passive"))
      (node (ref "P3") (pin "2") (pinfunction "-_2") (pintype "passive"))
      (node (ref "P4") (pin "2") (pinfunction "-_2") (pintype "passive"))
      (node (ref "P5") (pin "2") (pinfunction "-_2") (pintype "passive"))
      (node (ref "R13") (pin "1") (pinfunction "1_1") (pintype "passive"))
      (node (ref "R19") (pin "1") (pinfunction "1_1") (pintype "passive"))
      (node (ref "R21") (pin "1") (pinfunction "1_1") (pintype "passive"))
      (node (ref "R7") (pin "1") (pinfunction "1_1") (pintype "passive"))
      (node (ref "T1") (pin "2") (pinfunction "E_2") (pintype "passive"))
      (node (ref "T3") (pin "2") (pinfunction "E_2") (pintype "passive"))
      (node (ref "T4") (pin "2") (pinfunction "E_2") (pintype "passive"))
      (node (ref "U1") (pin "0") (pinfunction "PowerPAD_0") (pintype "passive"))
      (node (ref "U1") (pin "6") (pinfunction "GND_6") (pintype "passive"))
      (node (ref "U2") (pin "1") (pinfunction "GND_1") (pintype "passive"))
      (node (ref "U3") (pin "2") (pinfunction "GND_2") (pintype "passive"))
      (node (ref "U3") (pin "5") (pinfunction "SHDN_5") (pintype "passive"))
      (node (ref "U3") (pin "8") (pinfunction "RS_8") (pintype "passive"))
      (node (ref "U4") (pin "12") (pinfunction "VSSA_12") (pintype "passive"))
      (node (ref "U4") (pin "18") (pinfunction "VSS_2_18") (pintype "passive"))
      (node (ref "U4") (pin "63") (pinfunction "VSS_1_63") (pintype "passive"))
      (node (ref "U5") (pin "2") (pinfunction "GND_2") (pintype "passive"))
      (node (ref "U5") (pin "5") (pinfunction "SHDN_5") (pintype "passive"))
      (node (ref "U5") (pin "8") (pinfunction "RS_8") (pintype "passive"))
      (node (ref "X1") (pin "2") (pinfunction "GND_2") (pintype "passive"))
    )
    (net (code "40") (name "Net-(C16-Pad1)") (class "Default")
      (node (ref "C16") (pin "1") (pinfunction "1_1") (pintype "passive"))
      (node (ref "R8") (pin "1") (pinfunction "1_1") (pintype "passive"))
      (node (ref "R9") (pin "1") (pinfunction "1_1") (pintype "passive"))
    )
    (net (code "41") (name "Net-(C18-Pad1)") (class "Default")
      (node (ref "C18") (pin "1") (pinfunction "1_1") (pintype "passive"))
      (node (ref "R10") (pin "1") (pinfunction "1_1") (pintype "passive"))
      (node (ref "R11") (pin "1") (pinfunction "1_1") (pintype "passive"))
    )
    (net (code "42") (name "Net-(D3-A)") (class "Default")
      (node (ref "D3") (pin "1") (pinfunction "A_1") (pintype "passive"))
      (node (ref "J15") (pin "1") (pinfunction "1_1") (pintype "passive"))
      (node (ref "LED5") (pin "2") (pinfunction "C_2") (pintype "passive"))
      (node (ref "T4") (pin "3") (pinfunction "C_3") (pintype "passive"))
    )
    (net (code "43") (name "Net-(J5-Pad1)") (class "Default")
      (node (ref "J5") (pin "1") (pinfunction "1_1") (pintype "power_in"))
      (node (ref "R6") (pin "2") (pinfunction "2_2") (pintype "passive"))
    )
    (net (code "44") (name "Net-(LED1-A)") (class "Default")
      (node (ref "LED1") (pin "1") (pinfunction "A_1") (pintype "passive"))
      (node (ref "R1") (pin "1") (pinfunction "1_1") (pintype "passive"))
    )
    (net (code "45") (name "Net-(LED2-A)") (class "Default")
      (node (ref "LED2") (pin "1") (pinfunction "A_1") (pintype "passive"))
      (node (ref "R2") (pin "1") (pinfunction "1_1") (pintype "passive"))
    )
    (net (code "46") (name "Net-(LED3-A)") (class "Default")
      (node (ref "LED3") (pin "1") (pinfunction "A_1") (pintype "passive"))
      (node (ref "R4") (pin "1") (pinfunction "1_1") (pintype "passive"))
    )
    (net (code "47") (name "Net-(LED4-A)") (class "Default")
      (node (ref "LED4") (pin "1") (pinfunction "A_1") (pintype "passive"))
      (node (ref "R16") (pin "1") (pinfunction "1_1") (pintype "passive"))
      (node (ref "T2") (pin "2") (pinfunction "E_2") (pintype "passive"))
    )
    (net (code "48") (name "Net-(LED5-A)") (class "Default")
      (node (ref "LED5") (pin "1") (pinfunction "A_1") (pintype "passive"))
      (node (ref "R17") (pin "2") (pinfunction "2_2") (pintype "passive"))
    )
    (net (code "49") (name "Net-(T1-B)") (class "Default")
      (node (ref "R6") (pin "1") (pinfunction "1_1") (pintype "passive"))
      (node (ref "T1") (pin "1") (pinfunction "B_1") (pintype "passive"))
    )
    (net (code "50") (name "Net-(T2-B)") (class "Default")
      (node (ref "R15") (pin "1") (pinfunction "1_1") (pintype "passive"))
      (node (ref "R16") (pin "2") (pinfunction "2_2") (pintype "passive"))
      (node (ref "T2") (pin "1") (pinfunction "B_1") (pintype "passive"))
    )
    (net (code "51") (name "Net-(T2-C)") (class "Default")
      (node (ref "R12") (pin "2") (pinfunction "2_2") (pintype "passive"))
      (node (ref "T2") (pin "3") (pinfunction "C_3") (pintype "passive"))
    )
    (net (code "52") (name "Net-(T3-B)") (class "Default")
      (node (ref "C24") (pin "2") (pinfunction "2_2") (pintype "passive"))
      (node (ref "R18") (pin "2") (pinfunction "2_2") (pintype "passive"))
      (node (ref "R19") (pin "2") (pinfunction "2_2") (pintype "passive"))
      (node (ref "T3") (pin "1") (pinfunction "B_1") (pintype "passive"))
    )
    (net (code "53") (name "Net-(T3-C)") (class "Default")
      (node (ref "J14") (pin "2") (pinfunction "2_2") (pintype "passive"))
      (node (ref "T3") (pin "3") (pinfunction "C_3") (pintype "passive"))
    )
    (net (code "54") (name "Net-(T4-B)") (class "Default")
      (node (ref "C32") (pin "1") (pinfunction "1_1") (pintype "passive"))
      (node (ref "R20") (pin "2") (pinfunction "2_2") (pintype "passive"))
      (node (ref "R21") (pin "2") (pinfunction "2_2") (pintype "passive"))
      (node (ref "T4") (pin "1") (pinfunction "B_1") (pintype "passive"))
    )
    (net (code "55") (name "Net-(U1-BOOT)") (class "Default")
      (node (ref "C2") (pin "1") (pinfunction "1_1") (pintype "passive"))
      (node (ref "U1") (pin "1") (pinfunction "BOOT_1") (pintype "passive"))
    )
    (net (code "56") (name "Net-(U1-PH)") (class "Default")
      (node (ref "C2") (pin "2") (pinfunction "2_2") (pintype "passive"))
      (node (ref "D1") (pin "2") (pinfunction "2_2") (pintype "passive"))
      (node (ref "L1") (pin "1") (pinfunction "1_1") (pintype "passive"))
      (node (ref "U1") (pin "8") (pinfunction "PH_8") (pintype "passive"))
    )
    (net (code "57") (name "Net-(U1-VIN)") (class "Default")
      (node (ref "C3") (pin "2") (pinfunction "2_2") (pintype "passive"))
      (node (ref "C4") (pin "2") (pinfunction "2_2") (pintype "passive"))
      (node (ref "F1") (pin "2") (pinfunction "2_2") (pintype "passive"))
      (node (ref "R1") (pin "2") (pinfunction "2_2") (pintype "passive"))
      (node (ref "U1") (pin "7") (pinfunction "VIN_7") (pintype "passive"))
    )
    (net (code "58") (name "Net-(U1-VSENSE)") (class "Default")
      (node (ref "R3") (pin "1") (pinfunction "1_1") (pintype "passive"))
      (node (ref "R7") (pin "2") (pinfunction "2_2") (pintype "passive"))
      (node (ref "U1") (pin "4") (pinfunction "VSENSE_4") (pintype "passive"))
    )
    (net (code "59") (name "Net-(U4-BOOT0)") (class "Default")
      (node (ref "R13") (pin "2") (pinfunction "2_2") (pintype "passive"))
      (node (ref "U4") (pin "60") (pinfunction "BOOT0_60") (pintype "input"))
    )
    (net (code "60") (name "Net-(U4-PC8)") (class "Default")
      (node (ref "R15") (pin "2") (pinfunction "2_2") (pintype "passive"))
      (node (ref "U4") (pin "39") (pinfunction "PC8_39") (pintype "bidirectional"))
    )
    (net (code "61") (name "Net-(U4-VCAP_1)") (class "Default")
      (node (ref "C23") (pin "2") (pinfunction "2_2") (pintype "passive"))
      (node (ref "U4") (pin "31") (pinfunction "VCAP_1_31") (pintype "power_in"))
    )
    (net (code "62") (name "Net-(U4-VCAP_2)") (class "Default")
      (node (ref "C22") (pin "2") (pinfunction "2_2") (pintype "passive"))
      (node (ref "U4") (pin "47") (pinfunction "VCAP_2_47") (pintype "power_in"))
    )
    (net (code "63") (name "VDDA") (class "Default")
      (node (ref "C31") (pin "1") (pinfunction "1_1") (pintype "passive"))
      (node (ref "L2") (pin "2") (pinfunction "2_2") (pintype "passive"))
      (node (ref "U4") (pin "13") (pinfunction "VDDA_13") (pintype "power_in"))
    )
    (net (code "64") (name "unconnected-(J9-Pad1)") (class "Default")
      (node (ref "J9") (pin "1") (pinfunction "1_1") (pintype "passive"))
    )
    (net (code "65") (name "unconnected-(U1-ENA-Pad5)") (class "Default")
      (node (ref "U1") (pin "5") (pinfunction "ENA_5") (pintype "passive"))
    )
    (net (code "66") (name "unconnected-(U1-NC-Pad2)") (class "Default")
      (node (ref "U1") (pin "2") (pinfunction "NC_2") (pintype "passive"))
    )
    (net (code "67") (name "unconnected-(U1-NC-Pad3)") (class "Default")
      (node (ref "U1") (pin "3") (pinfunction "NC_3") (pintype "passive"))
    )
    (net (code "68") (name "unconnected-(U4-OSC_OUT{slash}PD1-Pad6)") (class "Default")
      (node (ref "U4") (pin "6") (pinfunction "OSC_OUT/PD1_6") (pintype "passive+no_connect"))
    )
    (net (code "69") (name "unconnected-(U4-PA0-WKUP-Pad14)") (class "Default")
      (node (ref "U4") (pin "14") (pinfunction "PA0-WKUP_14") (pintype "bidirectional"))
    )
    (net (code "70") (name "unconnected-(U4-PA1-Pad15)") (class "Default")
      (node (ref "U4") (pin "15") (pinfunction "PA1_15") (pintype "bidirectional"))
    )
    (net (code "71") (name "unconnected-(U4-PA2-Pad16)") (class "Default")
      (node (ref "U4") (pin "16") (pinfunction "PA2_16") (pintype "bidirectional"))
    )
    (net (code "72") (name "unconnected-(U4-PA5-Pad21)") (class "Default")
      (node (ref "U4") (pin "21") (pinfunction "PA5_21") (pintype "bidirectional"))
    )
    (net (code "73") (name "unconnected-(U4-PA6-Pad22)") (class "Default")
      (node (ref "U4") (pin "22") (pinfunction "PA6_22") (pintype "bidirectional"))
    )
    (net (code "74") (name "unconnected-(U4-PA7-Pad23)") (class "Default")
      (node (ref "U4") (pin "23") (pinfunction "PA7_23") (pintype "bidirectional"))
    )
    (net (code "75") (name "unconnected-(U4-PA11-Pad44)") (class "Default")
      (node (ref "U4") (pin "44") (pinfunction "PA11_44") (pintype "bidirectional"))
    )
    (net (code "76") (name "unconnected-(U4-PA12-Pad45)") (class "Default")
      (node (ref "U4") (pin "45") (pinfunction "PA12_45") (pintype "bidirectional"))
    )
    (net (code "77") (name "unconnected-(U4-PB2{slash}BOOT1-Pad28)") (class "Default")
      (node (ref "U4") (pin "28") (pinfunction "PB2/BOOT1_28") (pintype "bidirectional"))
    )
    (net (code "78") (name "unconnected-(U4-PB6-Pad58)") (class "Default")
      (node (ref "U4") (pin "58") (pinfunction "PB6_58") (pintype "bidirectional"))
    )
    (net (code "79") (name "unconnected-(U4-PB14-Pad35)") (class "Default")
      (node (ref "U4") (pin "35") (pinfunction "PB14_35") (pintype "bidirectional"))
    )
    (net (code "80") (name "unconnected-(U4-PB15-Pad36)") (class "Default")
      (node (ref "U4") (pin "36") (pinfunction "PB15_36") (pintype "bidirectional"))
    )
    (net (code "81") (name "unconnected-(U4-PC0-Pad8)") (class "Default")
      (node (ref "U4") (pin "8") (pinfunction "PC0_8") (pintype "bidirectional"))
    )
    (net (code "82") (name "unconnected-(U4-PC1-Pad9)") (class "Default")
      (node (ref "U4") (pin "9") (pinfunction "PC1_9") (pintype "bidirectional"))
    )
    (net (code "83") (name "unconnected-(U4-PC2-Pad10)") (class "Default")
      (node (ref "U4") (pin "10") (pinfunction "PC2_10") (pintype "bidirectional"))
    )
    (net (code "84") (name "unconnected-(U4-PC3-Pad11)") (class "Default")
      (node (ref "U4") (pin "11") (pinfunction "PC3_11") (pintype "bidirectional"))
    )
    (net (code "85") (name "unconnected-(U4-PC13-TAMPER-RTC-Pad2)") (class "Default")
      (node (ref "U4") (pin "2") (pinfunction "PC13-TAMPER-RTC_2") (pintype "bidirectional"))
    )
    (net (code "86") (name "unconnected-(U4-PC14-OSC32_IN-Pad3)") (class "Default")
      (node (ref "U4") (pin "3") (pinfunction "PC14-OSC32_IN_3") (pintype "bidirectional"))
    )
    (net (code "87") (name "unconnected-(U4-PC15-OSC32_OUT-Pad4)") (class "Default")
      (node (ref "U4") (pin "4") (pinfunction "PC15-OSC32_OUT_4") (pintype "bidirectional"))
    )
  )
)
